# Own_RPi_Streamerboard_pro_v1_3_Final_AR.net
KiCad netlist of a schematic drawn in EAGLE
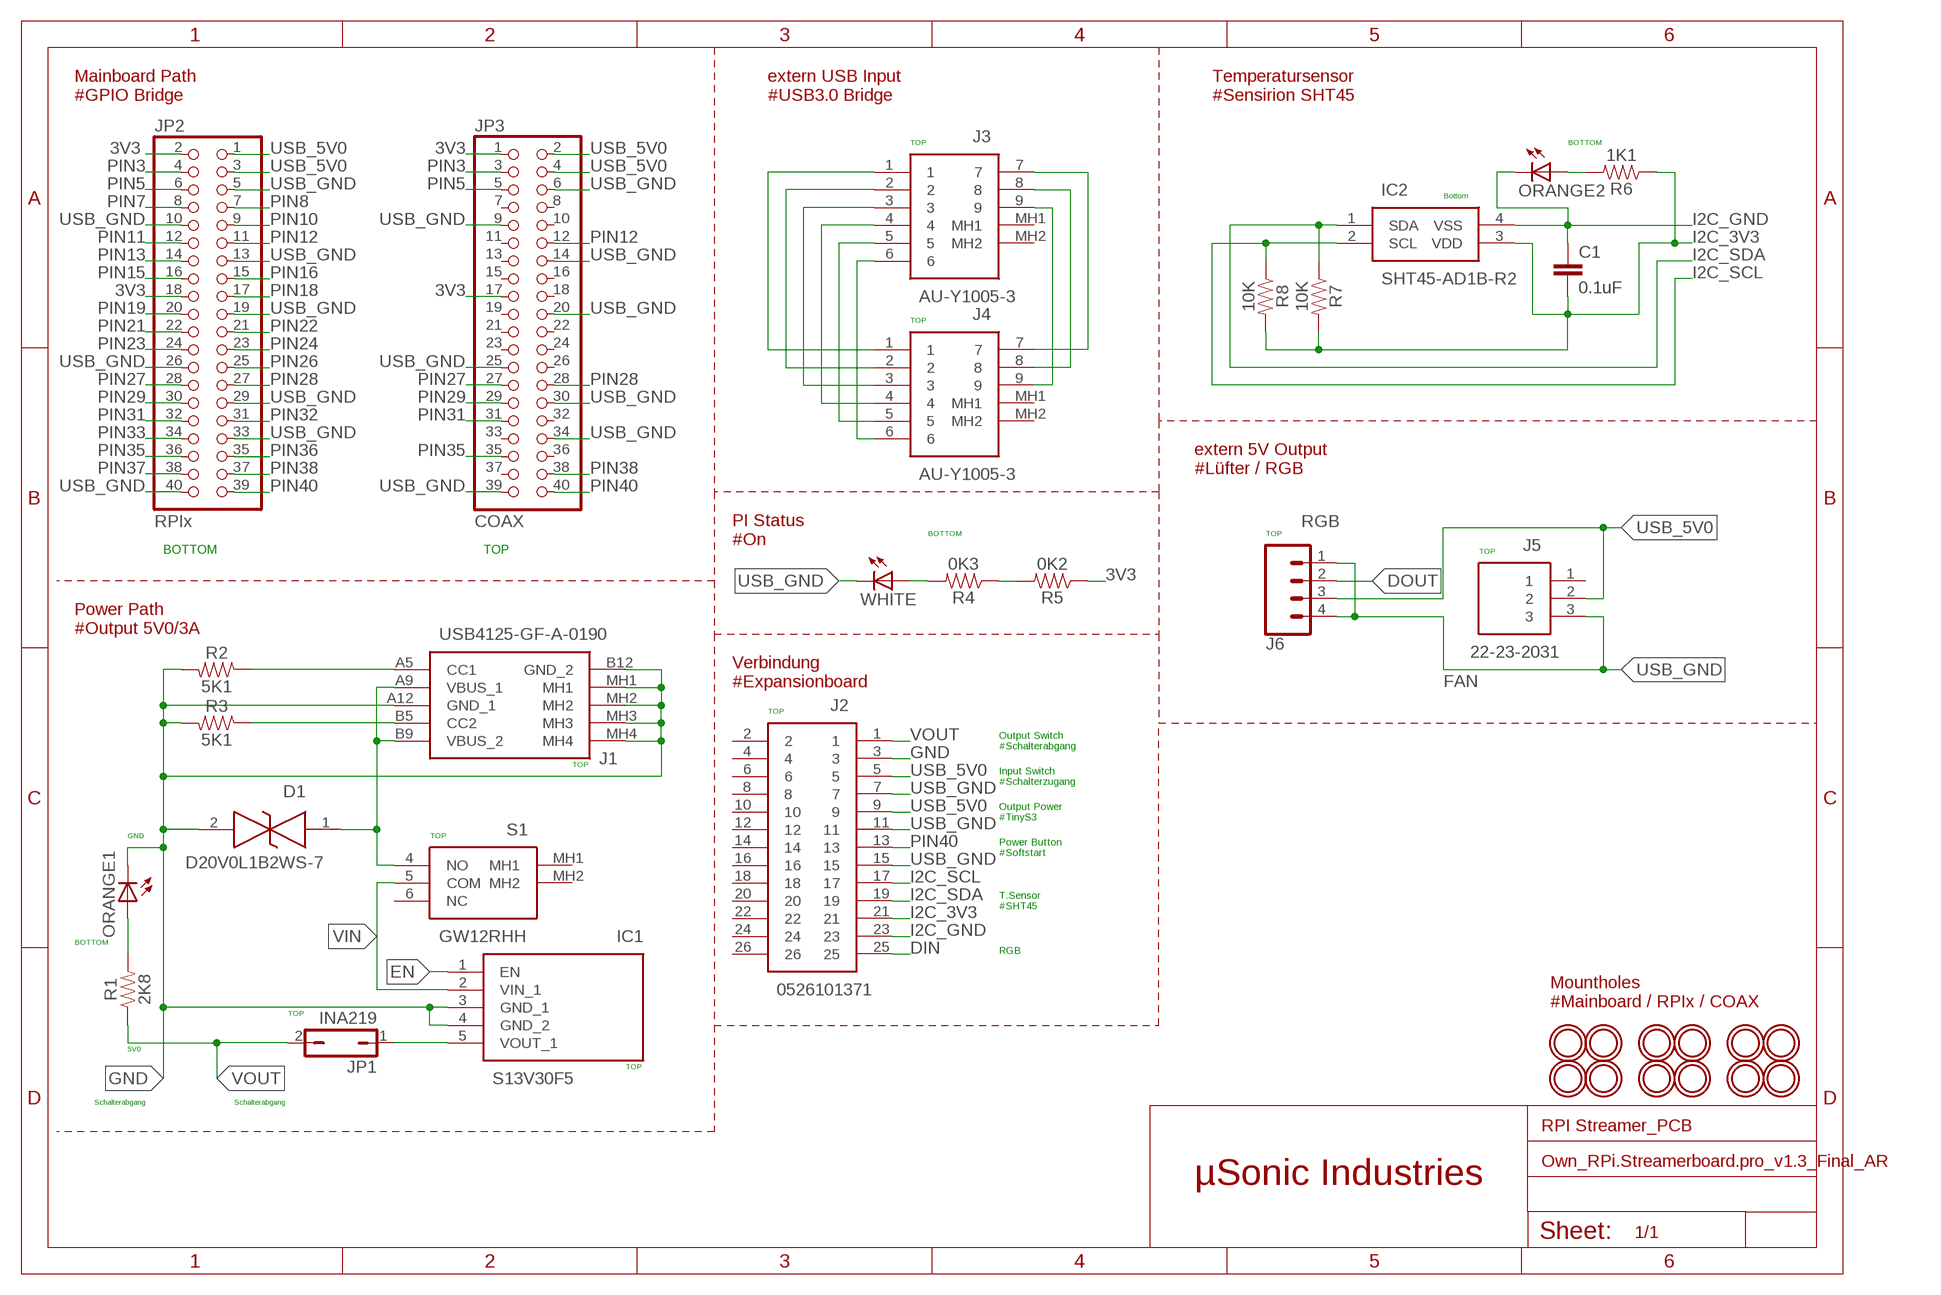
[diagram p0: schematic, sheet 1]

(export (version "E")
  (design (tool "Eeschema 10.0.6"))
  (components
    (comp (ref "C1")
      (value "0.1uF")
      (footprint "eagle-import:0805")
      (libsource (lib "eagle-import") (part "1.0UF-0805-25V-10%"))
    )
    (comp (ref "D1")
      (value "D20V0L1B2WS-7")
      (footprint "eagle-import:SOD2513X120N")
      (libsource (lib "eagle-import") (part "D20V0L1B2WS-7"))
    )
    (comp (ref "IC1")
      (value "S13V30F5")
      (footprint "eagle-import:S13V30F5")
      (libsource (lib "eagle-import") (part "S13V30F5"))
    )
    (comp (ref "IC2")
      (value "SHT45-AD1B-R2")
      (footprint "eagle-import:SHT45AD1BR2")
      (fields (field (name "MOUSER_PART_NUMBER") "403-SHT45-AD1B-R2"))
      (libsource (lib "eagle-import") (part "SHT45-AD1B-R2"))
    )
    (comp (ref "J1")
      (value "USB4125-GF-A-0190")
      (footprint "eagle-import:USB4125GFA0190")
      (fields (field (name "MOUSER_PART_NUMBER") "640-USB4125-GF-A-190"))
      (libsource (lib "eagle-import") (part "USB4125-GF-A-0190"))
    )
    (comp (ref "J2")
      (value "0526101371")
      (footprint "eagle-import:0526101371")
      (fields (field (name "ARROW_PART_NUMBER") "0526101433"))
      (libsource (lib "eagle-import") (part "0526101371"))
    )
    (comp (ref "J3")
      (value "AU-Y1005-3")
      (footprint "eagle-import:AUY10053")
      (libsource (lib "eagle-import") (part "AU-Y1005-3"))
    )
    (comp (ref "J4")
      (value "AU-Y1005-3")
      (footprint "eagle-import:AUY10053")
      (libsource (lib "eagle-import") (part "AU-Y1005-3"))
    )
    (comp (ref "J5")
      (value "22-23-2031")
      (footprint "eagle-import:SHDR3W82P0X254_1X3_747X635X818")
      (fields (field (name "MOUSER_PART_NUMBER") "538-22-23-2031"))
      (libsource (lib "eagle-import") (part "22-23-2031"))
    )
    (comp (ref "J6")
      (value "CONN_041X04_NO_SILK")
      (footprint "eagle-import:1X04_NO_SILK")
      (libsource (lib "eagle-import") (part "CONN_041X04_NO_SILK"))
    )
    (comp (ref "JP1")
      (value "INA219")
      (footprint "eagle-import:1X02_NO_SILK")
      (libsource (lib "eagle-import") (part "JP1Q2JP2"))
    )
    (comp (ref "JP2")
      (value "RPIx")
      (footprint "eagle-import:2X20-BIG")
      (libsource (lib "eagle-import") (part "PINHD-2X20-BIG"))
    )
    (comp (ref "JP3")
      (value "COAX")
      (footprint "eagle-import:2X20-BIG")
      (libsource (lib "eagle-import") (part "PINHD-2X20-BIG"))
    )
    (comp (ref "ORANGE1")
      (value "LEDCHIPLED_0805")
      (footprint "eagle-import:CHIPLED_0805")
      (libsource (lib "eagle-import") (part "LEDCHIPLED_0805"))
    )
    (comp (ref "ORANGE2")
      (value "LEDCHIPLED_0805")
      (footprint "eagle-import:CHIPLED_0805")
      (libsource (lib "eagle-import") (part "LEDCHIPLED_0805"))
    )
    (comp (ref "R1")
      (value "2K8")
      (footprint "eagle-import:0805")
      (libsource (lib "eagle-import") (part "RESISTOR0805"))
    )
    (comp (ref "R2")
      (value "5K1")
      (footprint "eagle-import:0805")
      (libsource (lib "eagle-import") (part "RESISTOR0805"))
    )
    (comp (ref "R3")
      (value "5K1")
      (footprint "eagle-import:0805")
      (libsource (lib "eagle-import") (part "RESISTOR0805"))
    )
    (comp (ref "R4")
      (value "0K3")
      (footprint "eagle-import:0805")
      (libsource (lib "eagle-import") (part "RESISTOR0805"))
    )
    (comp (ref "R5")
      (value "0K2")
      (footprint "eagle-import:0805")
      (libsource (lib "eagle-import") (part "RESISTOR0805"))
    )
    (comp (ref "R6")
      (value "1K1")
      (footprint "eagle-import:0805")
      (libsource (lib "eagle-import") (part "RESISTOR0805"))
    )
    (comp (ref "R7")
      (value "10K")
      (footprint "eagle-import:0805")
      (libsource (lib "eagle-import") (part "RESISTOR0805"))
    )
    (comp (ref "R8")
      (value "10K")
      (footprint "eagle-import:0805")
      (libsource (lib "eagle-import") (part "RESISTOR0805"))
    )
    (comp (ref "S1")
      (value "GW12RHH")
      (footprint "eagle-import:GW12RHH")
      (fields (field (name "MOUSER_PART_NUMBER") "633-GW12RHH"))
      (libsource (lib "eagle-import") (part "GW12RHH"))
    )
    (comp (ref "U$4")
      (value "MOUNTINGHOLE2.5")
      (footprint "eagle-import:MOUNTINGHOLE_2.5_PLATED")
      (libsource (lib "eagle-import") (part "MOUNTINGHOLE2.5"))
    )
    (comp (ref "U$5")
      (value "MOUNTINGHOLE2.5")
      (footprint "eagle-import:MOUNTINGHOLE_2.5_PLATED")
      (libsource (lib "eagle-import") (part "MOUNTINGHOLE2.5"))
    )
    (comp (ref "U$6")
      (value "MOUNTINGHOLE2.5")
      (footprint "eagle-import:MOUNTINGHOLE_2.5_PLATED")
      (libsource (lib "eagle-import") (part "MOUNTINGHOLE2.5"))
    )
    (comp (ref "U$7")
      (value "MOUNTINGHOLE2.5")
      (footprint "eagle-import:MOUNTINGHOLE_2.5_PLATED")
      (libsource (lib "eagle-import") (part "MOUNTINGHOLE2.5"))
    )
    (comp (ref "U$8")
      (value "MOUNTINGHOLE2.5")
      (footprint "eagle-import:MOUNTINGHOLE_2.5_PLATED")
      (libsource (lib "eagle-import") (part "MOUNTINGHOLE2.5"))
    )
    (comp (ref "U$10")
      (value "MOUNTINGHOLE2.5")
      (footprint "eagle-import:MOUNTINGHOLE_2.5_PLATED")
      (libsource (lib "eagle-import") (part "MOUNTINGHOLE2.5"))
    )
    (comp (ref "U$11")
      (value "MOUNTINGHOLE2.5")
      (footprint "eagle-import:MOUNTINGHOLE_2.5_PLATED")
      (libsource (lib "eagle-import") (part "MOUNTINGHOLE2.5"))
    )
    (comp (ref "U$13")
      (value "MOUNTINGHOLE2.5")
      (footprint "eagle-import:MOUNTINGHOLE_2.5_PLATED")
      (libsource (lib "eagle-import") (part "MOUNTINGHOLE2.5"))
    )
    (comp (ref "U$14")
      (value "MOUNTINGHOLE2.5")
      (footprint "eagle-import:MOUNTINGHOLE_2.5_PLATED")
      (libsource (lib "eagle-import") (part "MOUNTINGHOLE2.5"))
    )
    (comp (ref "U$15")
      (value "MOUNTINGHOLE2.5")
      (footprint "eagle-import:MOUNTINGHOLE_2.5_PLATED")
      (libsource (lib "eagle-import") (part "MOUNTINGHOLE2.5"))
    )
    (comp (ref "U$16")
      (value "MOUNTINGHOLE2.5")
      (footprint "eagle-import:MOUNTINGHOLE_2.5_PLATED")
      (libsource (lib "eagle-import") (part "MOUNTINGHOLE2.5"))
    )
    (comp (ref "U$17")
      (value "MOUNTINGHOLE2.5")
      (footprint "eagle-import:MOUNTINGHOLE_2.5_PLATED")
      (libsource (lib "eagle-import") (part "MOUNTINGHOLE2.5"))
    )
    (comp (ref "WHITE")
      (value "LEDCHIPLED_0805")
      (footprint "eagle-import:CHIPLED_0805")
      (libsource (lib "eagle-import") (part "LEDCHIPLED_0805"))
    )
  )
  (nets
    (net (code "1") (name "/3V3") (class "Default")
      (node (ref "JP2") (pin "18") (pinfunction "18_18") (pintype "passive"))
      (node (ref "JP2") (pin "2") (pinfunction "2_2") (pintype "passive"))
      (node (ref "JP3") (pin "1") (pinfunction "1_1") (pintype "passive"))
      (node (ref "JP3") (pin "17") (pinfunction "17_17") (pintype "passive"))
      (node (ref "R5") (pin "1") (pinfunction "1_1") (pintype "passive"))
    )
    (net (code "2") (name "/DIN") (class "Default")
      (node (ref "J2") (pin "25") (pinfunction "25_25") (pintype "bidirectional"))
    )
    (net (code "3") (name "/I2C_3V3") (class "Default")
      (node (ref "C1") (pin "2") (pinfunction "2_2") (pintype "passive"))
      (node (ref "IC2") (pin "3") (pinfunction "VDD_3") (pintype "bidirectional"))
      (node (ref "J2") (pin "21") (pinfunction "21_21") (pintype "bidirectional"))
      (node (ref "R6") (pin "1") (pinfunction "1_1") (pintype "passive"))
      (node (ref "R7") (pin "2") (pinfunction "2_2") (pintype "passive"))
      (node (ref "R8") (pin "2") (pinfunction "2_2") (pintype "passive"))
    )
    (net (code "4") (name "/I2C_GND") (class "Default")
      (node (ref "C1") (pin "1") (pinfunction "1_1") (pintype "passive"))
      (node (ref "IC2") (pin "4") (pinfunction "VSS_4") (pintype "bidirectional"))
      (node (ref "J2") (pin "23") (pinfunction "23_23") (pintype "bidirectional"))
      (node (ref "ORANGE2") (pin "C") (pinfunction "C_C") (pintype "passive"))
    )
    (net (code "5") (name "/I2C_SCL") (class "Default")
      (node (ref "IC2") (pin "2") (pinfunction "SCL_2") (pintype "bidirectional"))
      (node (ref "J2") (pin "17") (pinfunction "17_17") (pintype "bidirectional"))
      (node (ref "R8") (pin "1") (pinfunction "1_1") (pintype "passive"))
    )
    (net (code "6") (name "/I2C_SDA") (class "Default")
      (node (ref "IC2") (pin "1") (pinfunction "SDA_1") (pintype "bidirectional"))
      (node (ref "J2") (pin "19") (pinfunction "19_19") (pintype "bidirectional"))
      (node (ref "R7") (pin "1") (pinfunction "1_1") (pintype "passive"))
    )
    (net (code "7") (name "/PIN3") (class "Default")
      (node (ref "JP2") (pin "4") (pinfunction "4_4") (pintype "passive"))
      (node (ref "JP3") (pin "3") (pinfunction "3_3") (pintype "passive"))
    )
    (net (code "8") (name "/PIN5") (class "Default")
      (node (ref "JP2") (pin "6") (pinfunction "6_6") (pintype "passive"))
      (node (ref "JP3") (pin "5") (pinfunction "5_5") (pintype "passive"))
    )
    (net (code "9") (name "/PIN7") (class "Default")
      (node (ref "JP2") (pin "8") (pinfunction "8_8") (pintype "passive"))
    )
    (net (code "10") (name "/PIN8") (class "Default")
      (node (ref "JP2") (pin "7") (pinfunction "7_7") (pintype "passive"))
    )
    (net (code "11") (name "/PIN10") (class "Default")
      (node (ref "JP2") (pin "9") (pinfunction "9_9") (pintype "passive"))
    )
    (net (code "12") (name "/PIN11") (class "Default")
      (node (ref "JP2") (pin "12") (pinfunction "12_12") (pintype "passive"))
    )
    (net (code "13") (name "/PIN12") (class "Default")
      (node (ref "JP2") (pin "11") (pinfunction "11_11") (pintype "passive"))
      (node (ref "JP3") (pin "12") (pinfunction "12_12") (pintype "passive"))
    )
    (net (code "14") (name "/PIN13") (class "Default")
      (node (ref "JP2") (pin "14") (pinfunction "14_14") (pintype "passive"))
    )
    (net (code "15") (name "/PIN15") (class "Default")
      (node (ref "JP2") (pin "16") (pinfunction "16_16") (pintype "passive"))
    )
    (net (code "16") (name "/PIN16") (class "Default")
      (node (ref "JP2") (pin "15") (pinfunction "15_15") (pintype "passive"))
    )
    (net (code "17") (name "/PIN18") (class "Default")
      (node (ref "JP2") (pin "17") (pinfunction "17_17") (pintype "passive"))
    )
    (net (code "18") (name "/PIN19") (class "Default")
      (node (ref "JP2") (pin "20") (pinfunction "20_20") (pintype "passive"))
    )
    (net (code "19") (name "/PIN21") (class "Default")
      (node (ref "JP2") (pin "22") (pinfunction "22_22") (pintype "passive"))
    )
    (net (code "20") (name "/PIN22") (class "Default")
      (node (ref "JP2") (pin "21") (pinfunction "21_21") (pintype "passive"))
    )
    (net (code "21") (name "/PIN23") (class "Default")
      (node (ref "JP2") (pin "24") (pinfunction "24_24") (pintype "passive"))
    )
    (net (code "22") (name "/PIN24") (class "Default")
      (node (ref "JP2") (pin "23") (pinfunction "23_23") (pintype "passive"))
    )
    (net (code "23") (name "/PIN26") (class "Default")
      (node (ref "JP2") (pin "25") (pinfunction "25_25") (pintype "passive"))
    )
    (net (code "24") (name "/PIN27") (class "Default")
      (node (ref "JP2") (pin "28") (pinfunction "28_28") (pintype "passive"))
      (node (ref "JP3") (pin "27") (pinfunction "27_27") (pintype "passive"))
    )
    (net (code "25") (name "/PIN28") (class "Default")
      (node (ref "JP2") (pin "27") (pinfunction "27_27") (pintype "passive"))
      (node (ref "JP3") (pin "28") (pinfunction "28_28") (pintype "passive"))
    )
    (net (code "26") (name "/PIN29") (class "Default")
      (node (ref "JP2") (pin "30") (pinfunction "30_30") (pintype "passive"))
      (node (ref "JP3") (pin "29") (pinfunction "29_29") (pintype "passive"))
    )
    (net (code "27") (name "/PIN31") (class "Default")
      (node (ref "JP2") (pin "32") (pinfunction "32_32") (pintype "passive"))
      (node (ref "JP3") (pin "31") (pinfunction "31_31") (pintype "passive"))
    )
    (net (code "28") (name "/PIN32") (class "Default")
      (node (ref "JP2") (pin "31") (pinfunction "31_31") (pintype "passive"))
    )
    (net (code "29") (name "/PIN33") (class "Default")
      (node (ref "JP2") (pin "34") (pinfunction "34_34") (pintype "passive"))
    )
    (net (code "30") (name "/PIN35") (class "Default")
      (node (ref "JP2") (pin "36") (pinfunction "36_36") (pintype "passive"))
      (node (ref "JP3") (pin "35") (pinfunction "35_35") (pintype "passive"))
    )
    (net (code "31") (name "/PIN36") (class "Default")
      (node (ref "JP2") (pin "35") (pinfunction "35_35") (pintype "passive"))
    )
    (net (code "32") (name "/PIN37") (class "Default")
      (node (ref "JP2") (pin "38") (pinfunction "38_38") (pintype "passive"))
    )
    (net (code "33") (name "/PIN38") (class "Default")
      (node (ref "JP2") (pin "37") (pinfunction "37_37") (pintype "passive"))
      (node (ref "JP3") (pin "38") (pinfunction "38_38") (pintype "passive"))
    )
    (net (code "34") (name "/PIN40") (class "Default")
      (node (ref "J2") (pin "13") (pinfunction "13_13") (pintype "bidirectional"))
      (node (ref "JP2") (pin "39") (pinfunction "39_39") (pintype "passive"))
      (node (ref "JP3") (pin "40") (pinfunction "40_40") (pintype "passive"))
    )
    (net (code "35") (name "DOUT") (class "Default")
      (node (ref "J6") (pin "2") (pinfunction "2_2") (pintype "passive"))
    )
    (net (code "36") (name "EN") (class "Default")
      (node (ref "IC1") (pin "1") (pinfunction "EN_1") (pintype "bidirectional"))
    )
    (net (code "37") (name "GND") (class "Default")
      (node (ref "D1") (pin "2") (pinfunction "2_2") (pintype "bidirectional"))
      (node (ref "IC1") (pin "3") (pinfunction "GND_1_3") (pintype "bidirectional"))
      (node (ref "IC1") (pin "4") (pinfunction "GND_2_4") (pintype "bidirectional"))
      (node (ref "J1") (pin "A12") (pinfunction "GND_1_A12") (pintype "bidirectional"))
      (node (ref "J1") (pin "B12") (pinfunction "GND_2_B12") (pintype "bidirectional"))
      (node (ref "J1") (pin "MH1") (pinfunction "MH1_MH1") (pintype "bidirectional"))
      (node (ref "J1") (pin "MH2") (pinfunction "MH2_MH2") (pintype "bidirectional"))
      (node (ref "J1") (pin "MH3") (pinfunction "MH3_MH3") (pintype "bidirectional"))
      (node (ref "J1") (pin "MH4") (pinfunction "MH4_MH4") (pintype "bidirectional"))
      (node (ref "J2") (pin "3") (pinfunction "3_3") (pintype "bidirectional"))
      (node (ref "ORANGE1") (pin "C") (pinfunction "C_C") (pintype "passive"))
      (node (ref "R2") (pin "2") (pinfunction "2_2") (pintype "passive"))
      (node (ref "R3") (pin "2") (pinfunction "2_2") (pintype "passive"))
    )
    (net (code "38") (name "Net-(IC1-VOUT_1)") (class "Default")
      (node (ref "IC1") (pin "5") (pinfunction "VOUT_1_5") (pintype "bidirectional"))
      (node (ref "JP1") (pin "1") (pinfunction "1_1") (pintype "passive"))
    )
    (net (code "39") (name "Net-(J1-CC1)") (class "Default")
      (node (ref "J1") (pin "A5") (pinfunction "CC1_A5") (pintype "bidirectional"))
      (node (ref "R2") (pin "1") (pinfunction "1_1") (pintype "passive"))
    )
    (net (code "40") (name "Net-(J1-CC2)") (class "Default")
      (node (ref "J1") (pin "B5") (pinfunction "CC2_B5") (pintype "bidirectional"))
      (node (ref "R3") (pin "1") (pinfunction "1_1") (pintype "passive"))
    )
    (net (code "41") (name "Net-(J1-VBUS_1)") (class "Default")
      (node (ref "D1") (pin "1") (pinfunction "1_1") (pintype "bidirectional"))
      (node (ref "J1") (pin "A9") (pinfunction "VBUS_1_A9") (pintype "bidirectional"))
      (node (ref "J1") (pin "B9") (pinfunction "VBUS_2_B9") (pintype "bidirectional"))
      (node (ref "S1") (pin "4") (pinfunction "NO_4") (pintype "bidirectional"))
    )
    (net (code "42") (name "Net-(J3-Pad1)") (class "Default")
      (node (ref "J3") (pin "1") (pinfunction "1_1") (pintype "bidirectional"))
      (node (ref "J4") (pin "1") (pinfunction "1_1") (pintype "bidirectional"))
    )
    (net (code "43") (name "Net-(J3-Pad2)") (class "Default")
      (node (ref "J3") (pin "2") (pinfunction "2_2") (pintype "bidirectional"))
      (node (ref "J4") (pin "2") (pinfunction "2_2") (pintype "bidirectional"))
    )
    (net (code "44") (name "Net-(J3-Pad3)") (class "Default")
      (node (ref "J3") (pin "3") (pinfunction "3_3") (pintype "bidirectional"))
      (node (ref "J4") (pin "3") (pinfunction "3_3") (pintype "bidirectional"))
    )
    (net (code "45") (name "Net-(J3-Pad4)") (class "Default")
      (node (ref "J3") (pin "4") (pinfunction "4_4") (pintype "bidirectional"))
      (node (ref "J4") (pin "4") (pinfunction "4_4") (pintype "bidirectional"))
    )
    (net (code "46") (name "Net-(J3-Pad5)") (class "Default")
      (node (ref "J3") (pin "5") (pinfunction "5_5") (pintype "bidirectional"))
      (node (ref "J4") (pin "5") (pinfunction "5_5") (pintype "bidirectional"))
    )
    (net (code "47") (name "Net-(J3-Pad6)") (class "Default")
      (node (ref "J3") (pin "6") (pinfunction "6_6") (pintype "bidirectional"))
      (node (ref "J4") (pin "6") (pinfunction "6_6") (pintype "bidirectional"))
    )
    (net (code "48") (name "Net-(J3-Pad7)") (class "Default")
      (node (ref "J3") (pin "7") (pinfunction "7_7") (pintype "bidirectional"))
      (node (ref "J4") (pin "7") (pinfunction "7_7") (pintype "bidirectional"))
    )
    (net (code "49") (name "Net-(J3-Pad8)") (class "Default")
      (node (ref "J3") (pin "8") (pinfunction "8_8") (pintype "bidirectional"))
      (node (ref "J4") (pin "8") (pinfunction "8_8") (pintype "bidirectional"))
    )
    (net (code "50") (name "Net-(J3-Pad9)") (class "Default")
      (node (ref "J3") (pin "9") (pinfunction "9_9") (pintype "bidirectional"))
      (node (ref "J4") (pin "9") (pinfunction "9_9") (pintype "bidirectional"))
    )
    (net (code "51") (name "Net-(ORANGE1-PadA)") (class "Default")
      (node (ref "ORANGE1") (pin "A") (pinfunction "A_A") (pintype "passive"))
      (node (ref "R1") (pin "2") (pinfunction "2_2") (pintype "passive"))
    )
    (net (code "52") (name "Net-(ORANGE2-PadA)") (class "Default")
      (node (ref "ORANGE2") (pin "A") (pinfunction "A_A") (pintype "passive"))
      (node (ref "R6") (pin "2") (pinfunction "2_2") (pintype "passive"))
    )
    (net (code "53") (name "Net-(R4-Pad1)") (class "Default")
      (node (ref "R4") (pin "1") (pinfunction "1_1") (pintype "passive"))
      (node (ref "R5") (pin "2") (pinfunction "2_2") (pintype "passive"))
    )
    (net (code "54") (name "Net-(R4-Pad2)") (class "Default")
      (node (ref "R4") (pin "2") (pinfunction "2_2") (pintype "passive"))
      (node (ref "WHITE") (pin "A") (pinfunction "A_A") (pintype "passive"))
    )
    (net (code "55") (name "USB_5V0") (class "Default")
      (node (ref "J2") (pin "5") (pinfunction "5_5") (pintype "bidirectional"))
      (node (ref "J2") (pin "9") (pinfunction "9_9") (pintype "bidirectional"))
      (node (ref "J5") (pin "2") (pinfunction "2_2") (pintype "bidirectional"))
      (node (ref "J6") (pin "3") (pinfunction "3_3") (pintype "passive"))
      (node (ref "JP2") (pin "1") (pinfunction "1_1") (pintype "passive"))
      (node (ref "JP2") (pin "3") (pinfunction "3_3") (pintype "passive"))
      (node (ref "JP3") (pin "2") (pinfunction "2_2") (pintype "passive"))
      (node (ref "JP3") (pin "4") (pinfunction "4_4") (pintype "passive"))
    )
    (net (code "56") (name "USB_GND") (class "Default")
      (node (ref "J2") (pin "11") (pinfunction "11_11") (pintype "bidirectional"))
      (node (ref "J2") (pin "15") (pinfunction "15_15") (pintype "bidirectional"))
      (node (ref "J2") (pin "7") (pinfunction "7_7") (pintype "bidirectional"))
      (node (ref "J5") (pin "3") (pinfunction "3_3") (pintype "bidirectional"))
      (node (ref "J6") (pin "1") (pinfunction "1_1") (pintype "passive"))
      (node (ref "J6") (pin "4") (pinfunction "4_4") (pintype "passive"))
      (node (ref "JP2") (pin "10") (pinfunction "10_10") (pintype "passive"))
      (node (ref "JP2") (pin "13") (pinfunction "13_13") (pintype "passive"))
      (node (ref "JP2") (pin "19") (pinfunction "19_19") (pintype "passive"))
      (node (ref "JP2") (pin "26") (pinfunction "26_26") (pintype "passive"))
      (node (ref "JP2") (pin "29") (pinfunction "29_29") (pintype "passive"))
      (node (ref "JP2") (pin "33") (pinfunction "33_33") (pintype "passive"))
      (node (ref "JP2") (pin "40") (pinfunction "40_40") (pintype "passive"))
      (node (ref "JP2") (pin "5") (pinfunction "5_5") (pintype "passive"))
      (node (ref "JP3") (pin "14") (pinfunction "14_14") (pintype "passive"))
      (node (ref "JP3") (pin "20") (pinfunction "20_20") (pintype "passive"))
      (node (ref "JP3") (pin "25") (pinfunction "25_25") (pintype "passive"))
      (node (ref "JP3") (pin "30") (pinfunction "30_30") (pintype "passive"))
      (node (ref "JP3") (pin "34") (pinfunction "34_34") (pintype "passive"))
      (node (ref "JP3") (pin "39") (pinfunction "39_39") (pintype "passive"))
      (node (ref "JP3") (pin "6") (pinfunction "6_6") (pintype "passive"))
      (node (ref "JP3") (pin "9") (pinfunction "9_9") (pintype "passive"))
      (node (ref "WHITE") (pin "C") (pinfunction "C_C") (pintype "passive"))
    )
    (net (code "57") (name "VIN") (class "Default")
      (node (ref "IC1") (pin "2") (pinfunction "VIN_1_2") (pintype "bidirectional"))
      (node (ref "S1") (pin "5") (pinfunction "COM_5") (pintype "bidirectional"))
    )
    (net (code "58") (name "VOUT") (class "Default")
      (node (ref "J2") (pin "1") (pinfunction "1_1") (pintype "bidirectional"))
      (node (ref "JP1") (pin "2") (pinfunction "2_2") (pintype "passive"))
      (node (ref "R1") (pin "1") (pinfunction "1_1") (pintype "passive"))
    )
    (net (code "59") (name "unconnected-(J2-Pad2)") (class "Default")
      (node (ref "J2") (pin "2") (pinfunction "2_2") (pintype "bidirectional"))
    )
    (net (code "60") (name "unconnected-(J2-Pad4)") (class "Default")
      (node (ref "J2") (pin "4") (pinfunction "4_4") (pintype "bidirectional"))
    )
    (net (code "61") (name "unconnected-(J2-Pad6)") (class "Default")
      (node (ref "J2") (pin "6") (pinfunction "6_6") (pintype "bidirectional"))
    )
    (net (code "62") (name "unconnected-(J2-Pad8)") (class "Default")
      (node (ref "J2") (pin "8") (pinfunction "8_8") (pintype "bidirectional"))
    )
    (net (code "63") (name "unconnected-(J2-Pad10)") (class "Default")
      (node (ref "J2") (pin "10") (pinfunction "10_10") (pintype "bidirectional"))
    )
    (net (code "64") (name "unconnected-(J2-Pad12)") (class "Default")
      (node (ref "J2") (pin "12") (pinfunction "12_12") (pintype "bidirectional"))
    )
    (net (code "65") (name "unconnected-(J2-Pad14)") (class "Default")
      (node (ref "J2") (pin "14") (pinfunction "14_14") (pintype "bidirectional"))
    )
    (net (code "66") (name "unconnected-(J2-Pad16)") (class "Default")
      (node (ref "J2") (pin "16") (pinfunction "16_16") (pintype "bidirectional"))
    )
    (net (code "67") (name "unconnected-(J2-Pad18)") (class "Default")
      (node (ref "J2") (pin "18") (pinfunction "18_18") (pintype "bidirectional"))
    )
    (net (code "68") (name "unconnected-(J2-Pad20)") (class "Default")
      (node (ref "J2") (pin "20") (pinfunction "20_20") (pintype "bidirectional"))
    )
    (net (code "69") (name "unconnected-(J2-Pad22)") (class "Default")
      (node (ref "J2") (pin "22") (pinfunction "22_22") (pintype "bidirectional"))
    )
    (net (code "70") (name "unconnected-(J2-Pad24)") (class "Default")
      (node (ref "J2") (pin "24") (pinfunction "24_24") (pintype "bidirectional"))
    )
    (net (code "71") (name "unconnected-(J2-Pad26)") (class "Default")
      (node (ref "J2") (pin "26") (pinfunction "26_26") (pintype "bidirectional"))
    )
    (net (code "72") (name "unconnected-(J3-PadMH1)") (class "Default")
      (node (ref "J3") (pin "MH1") (pinfunction "MH1_MH1") (pintype "bidirectional"))
    )
    (net (code "73") (name "unconnected-(J3-PadMH2)") (class "Default")
      (node (ref "J3") (pin "MH2") (pinfunction "MH2_MH2") (pintype "bidirectional"))
    )
    (net (code "74") (name "unconnected-(J4-PadMH1)") (class "Default")
      (node (ref "J4") (pin "MH1") (pinfunction "MH1_MH1") (pintype "bidirectional"))
    )
    (net (code "75") (name "unconnected-(J4-PadMH2)") (class "Default")
      (node (ref "J4") (pin "MH2") (pinfunction "MH2_MH2") (pintype "bidirectional"))
    )
    (net (code "76") (name "unconnected-(J5-Pad1)") (class "Default")
      (node (ref "J5") (pin "1") (pinfunction "1_1") (pintype "bidirectional"))
    )
    (net (code "77") (name "unconnected-(JP3-Pad7)") (class "Default")
      (node (ref "JP3") (pin "7") (pinfunction "7_7") (pintype "passive"))
    )
    (net (code "78") (name "unconnected-(JP3-Pad8)") (class "Default")
      (node (ref "JP3") (pin "8") (pinfunction "8_8") (pintype "passive"))
    )
    (net (code "79") (name "unconnected-(JP3-Pad10)") (class "Default")
      (node (ref "JP3") (pin "10") (pinfunction "10_10") (pintype "passive"))
    )
    (net (code "80") (name "unconnected-(JP3-Pad11)") (class "Default")
      (node (ref "JP3") (pin "11") (pinfunction "11_11") (pintype "passive"))
    )
    (net (code "81") (name "unconnected-(JP3-Pad13)") (class "Default")
      (node (ref "JP3") (pin "13") (pinfunction "13_13") (pintype "passive"))
    )
    (net (code "82") (name "unconnected-(JP3-Pad15)") (class "Default")
      (node (ref "JP3") (pin "15") (pinfunction "15_15") (pintype "passive"))
    )
    (net (code "83") (name "unconnected-(JP3-Pad16)") (class "Default")
      (node (ref "JP3") (pin "16") (pinfunction "16_16") (pintype "passive"))
    )
    (net (code "84") (name "unconnected-(JP3-Pad18)") (class "Default")
      (node (ref "JP3") (pin "18") (pinfunction "18_18") (pintype "passive"))
    )
    (net (code "85") (name "unconnected-(JP3-Pad19)") (class "Default")
      (node (ref "JP3") (pin "19") (pinfunction "19_19") (pintype "passive"))
    )
    (net (code "86") (name "unconnected-(JP3-Pad21)") (class "Default")
      (node (ref "JP3") (pin "21") (pinfunction "21_21") (pintype "passive"))
    )
    (net (code "87") (name "unconnected-(JP3-Pad22)") (class "Default")
      (node (ref "JP3") (pin "22") (pinfunction "22_22") (pintype "passive"))
    )
    (net (code "88") (name "unconnected-(JP3-Pad23)") (class "Default")
      (node (ref "JP3") (pin "23") (pinfunction "23_23") (pintype "passive"))
    )
    (net (code "89") (name "unconnected-(JP3-Pad24)") (class "Default")
      (node (ref "JP3") (pin "24") (pinfunction "24_24") (pintype "passive"))
    )
    (net (code "90") (name "unconnected-(JP3-Pad26)") (class "Default")
      (node (ref "JP3") (pin "26") (pinfunction "26_26") (pintype "passive"))
    )
    (net (code "91") (name "unconnected-(JP3-Pad32)") (class "Default")
      (node (ref "JP3") (pin "32") (pinfunction "32_32") (pintype "passive"))
    )
    (net (code "92") (name "unconnected-(JP3-Pad33)") (class "Default")
      (node (ref "JP3") (pin "33") (pinfunction "33_33") (pintype "passive"))
    )
    (net (code "93") (name "unconnected-(JP3-Pad36)") (class "Default")
      (node (ref "JP3") (pin "36") (pinfunction "36_36") (pintype "passive"))
    )
    (net (code "94") (name "unconnected-(JP3-Pad37)") (class "Default")
      (node (ref "JP3") (pin "37") (pinfunction "37_37") (pintype "passive"))
    )
    (net (code "95") (name "unconnected-(S1-NC-Pad6)") (class "Default")
      (node (ref "S1") (pin "6") (pinfunction "NC_6") (pintype "no_connect"))
    )
    (net (code "96") (name "unconnected-(S1-PadMH1)") (class "Default")
      (node (ref "S1") (pin "MH1") (pinfunction "MH1_MH1") (pintype "bidirectional"))
    )
    (net (code "97") (name "unconnected-(S1-PadMH2)") (class "Default")
      (node (ref "S1") (pin "MH2") (pinfunction "MH2_MH2") (pintype "bidirectional"))
    )
  )
)
